# icy-gecko.net
KiCad netlist of a schematic drawn in EAGLE
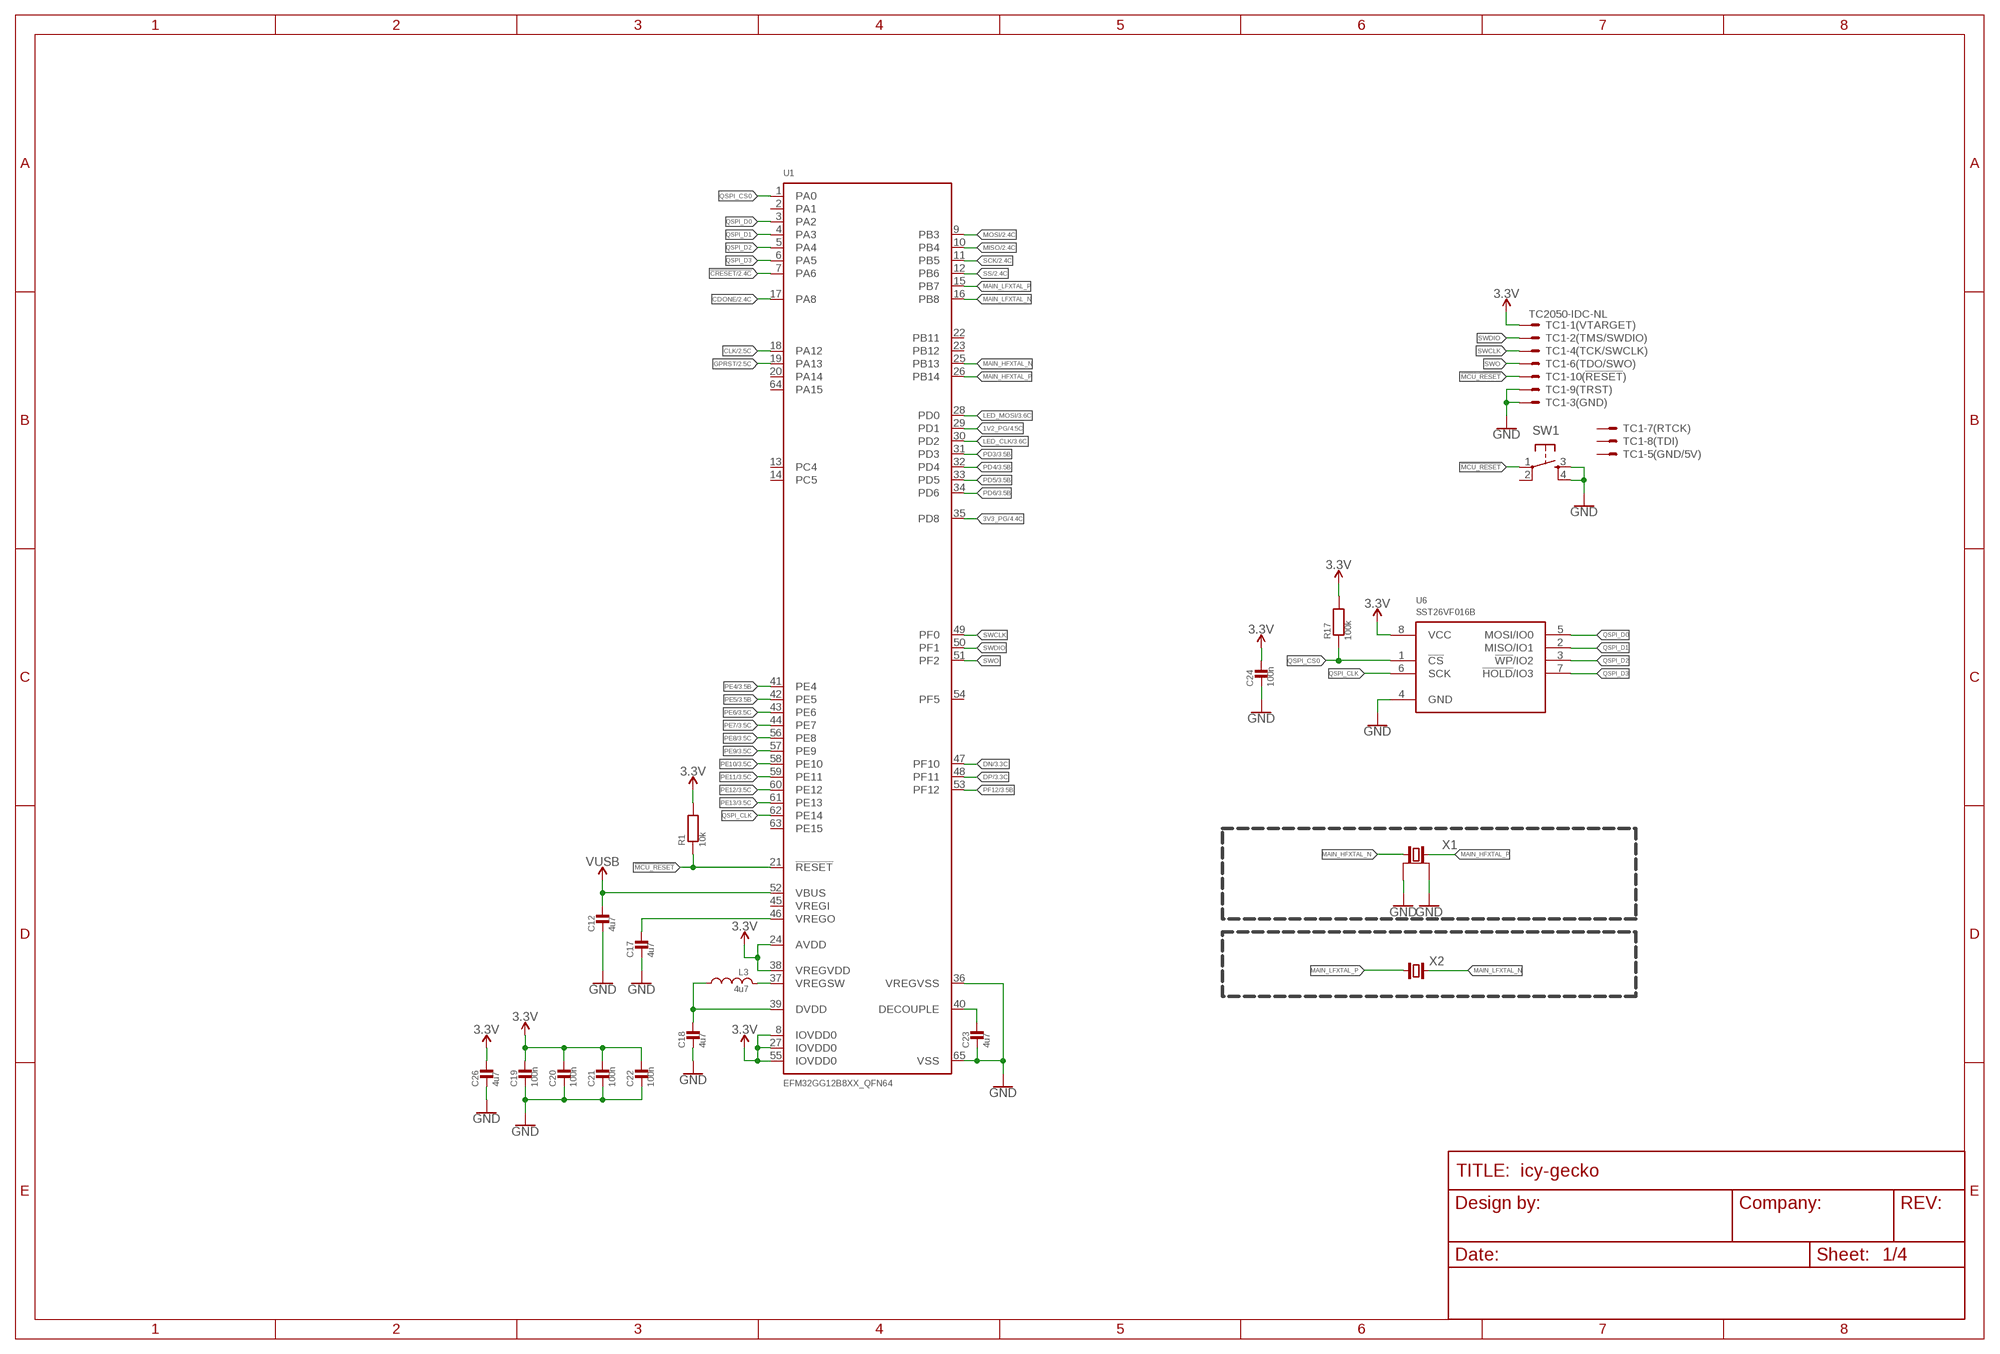
[diagram p0: schematic, sheet 1]
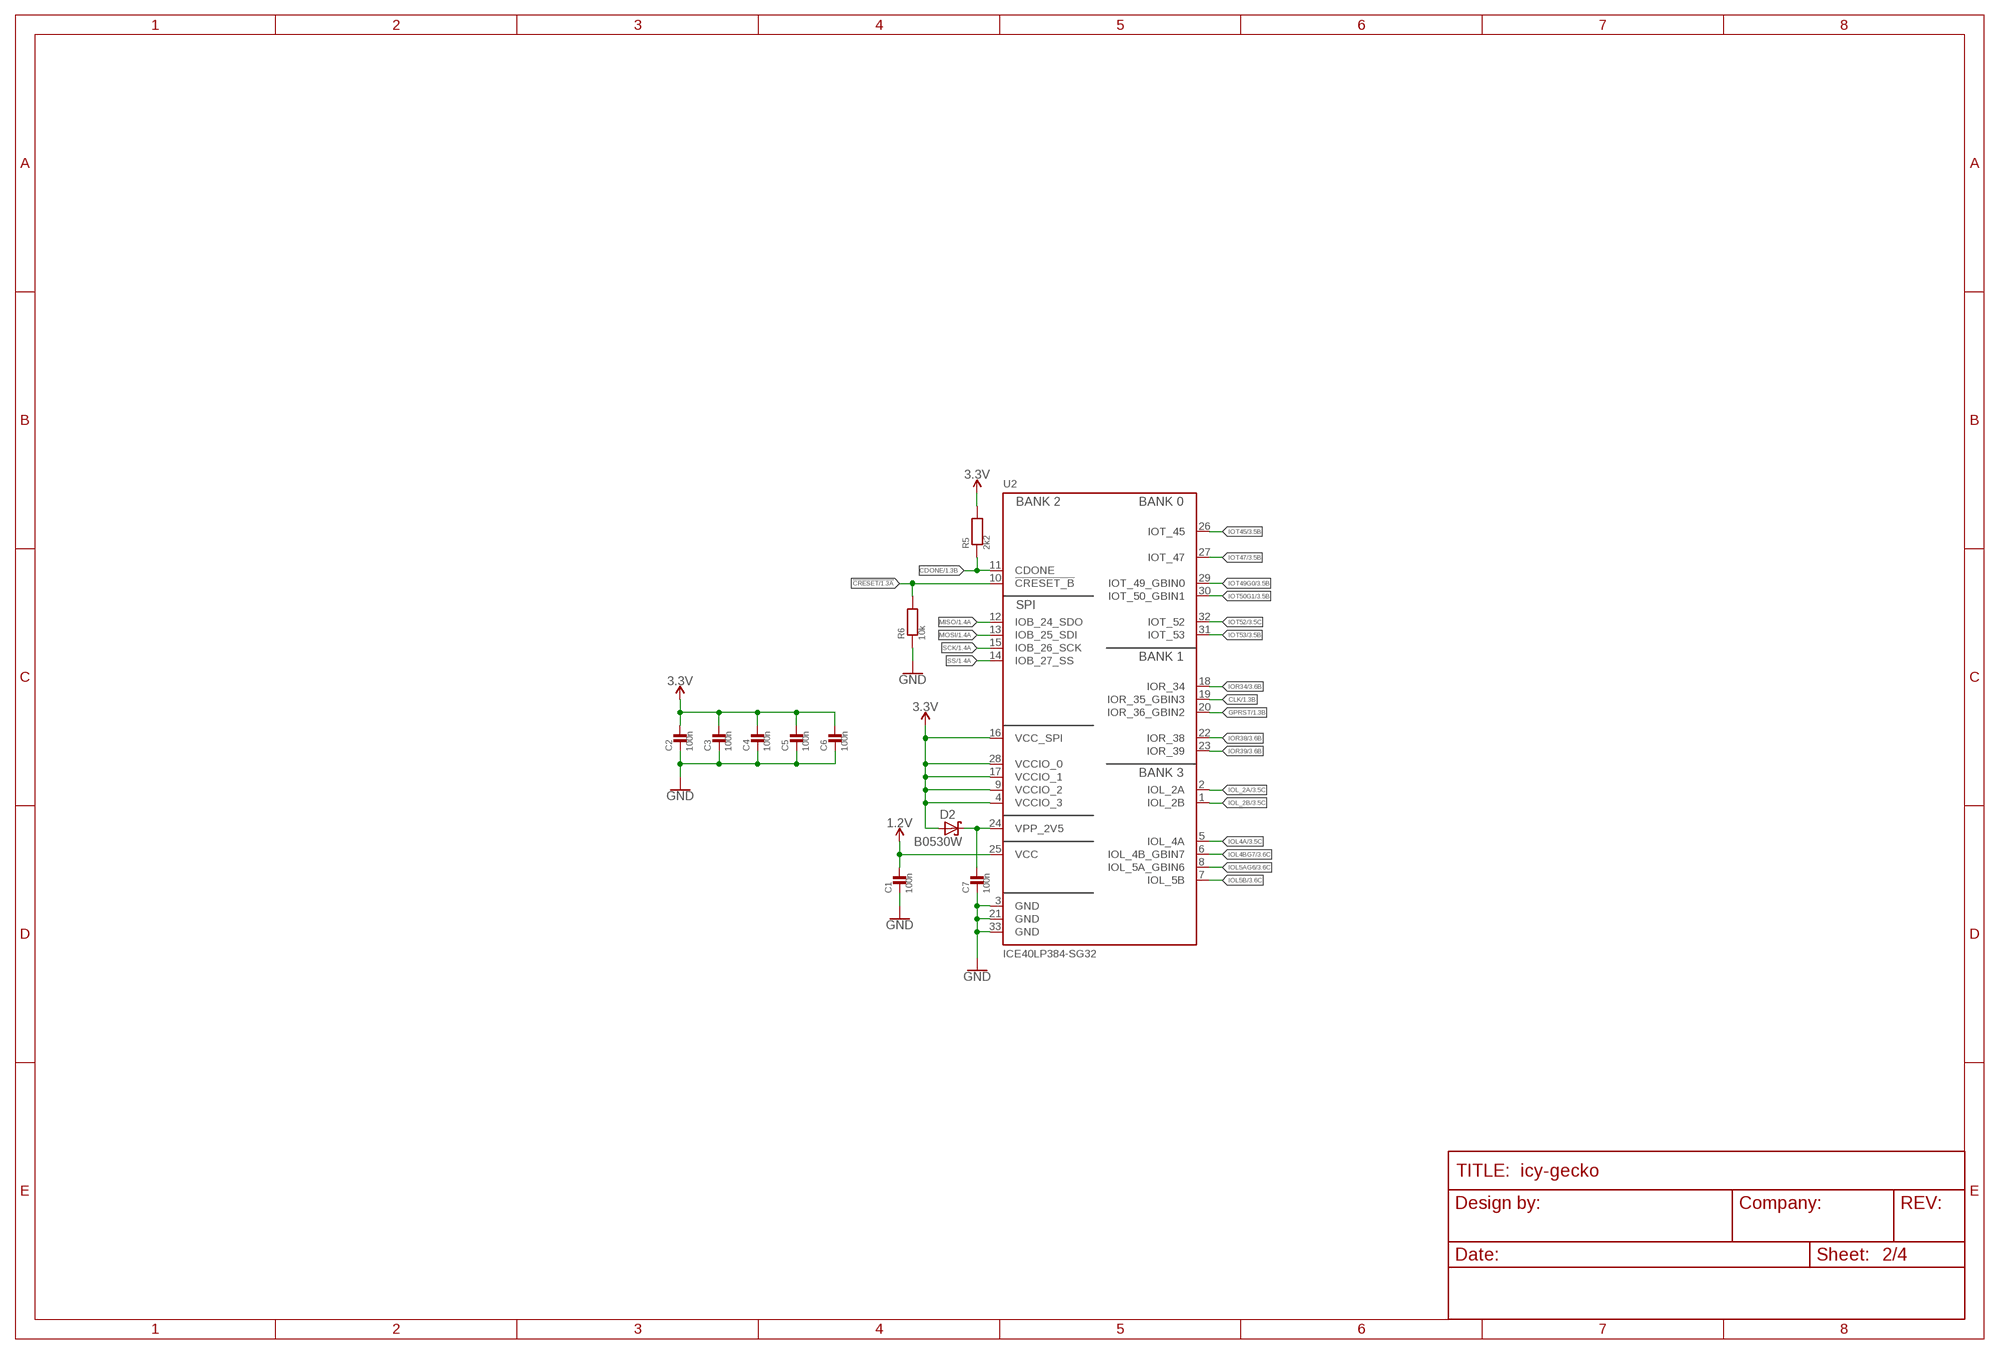
[diagram p1: schematic, sheet 2]
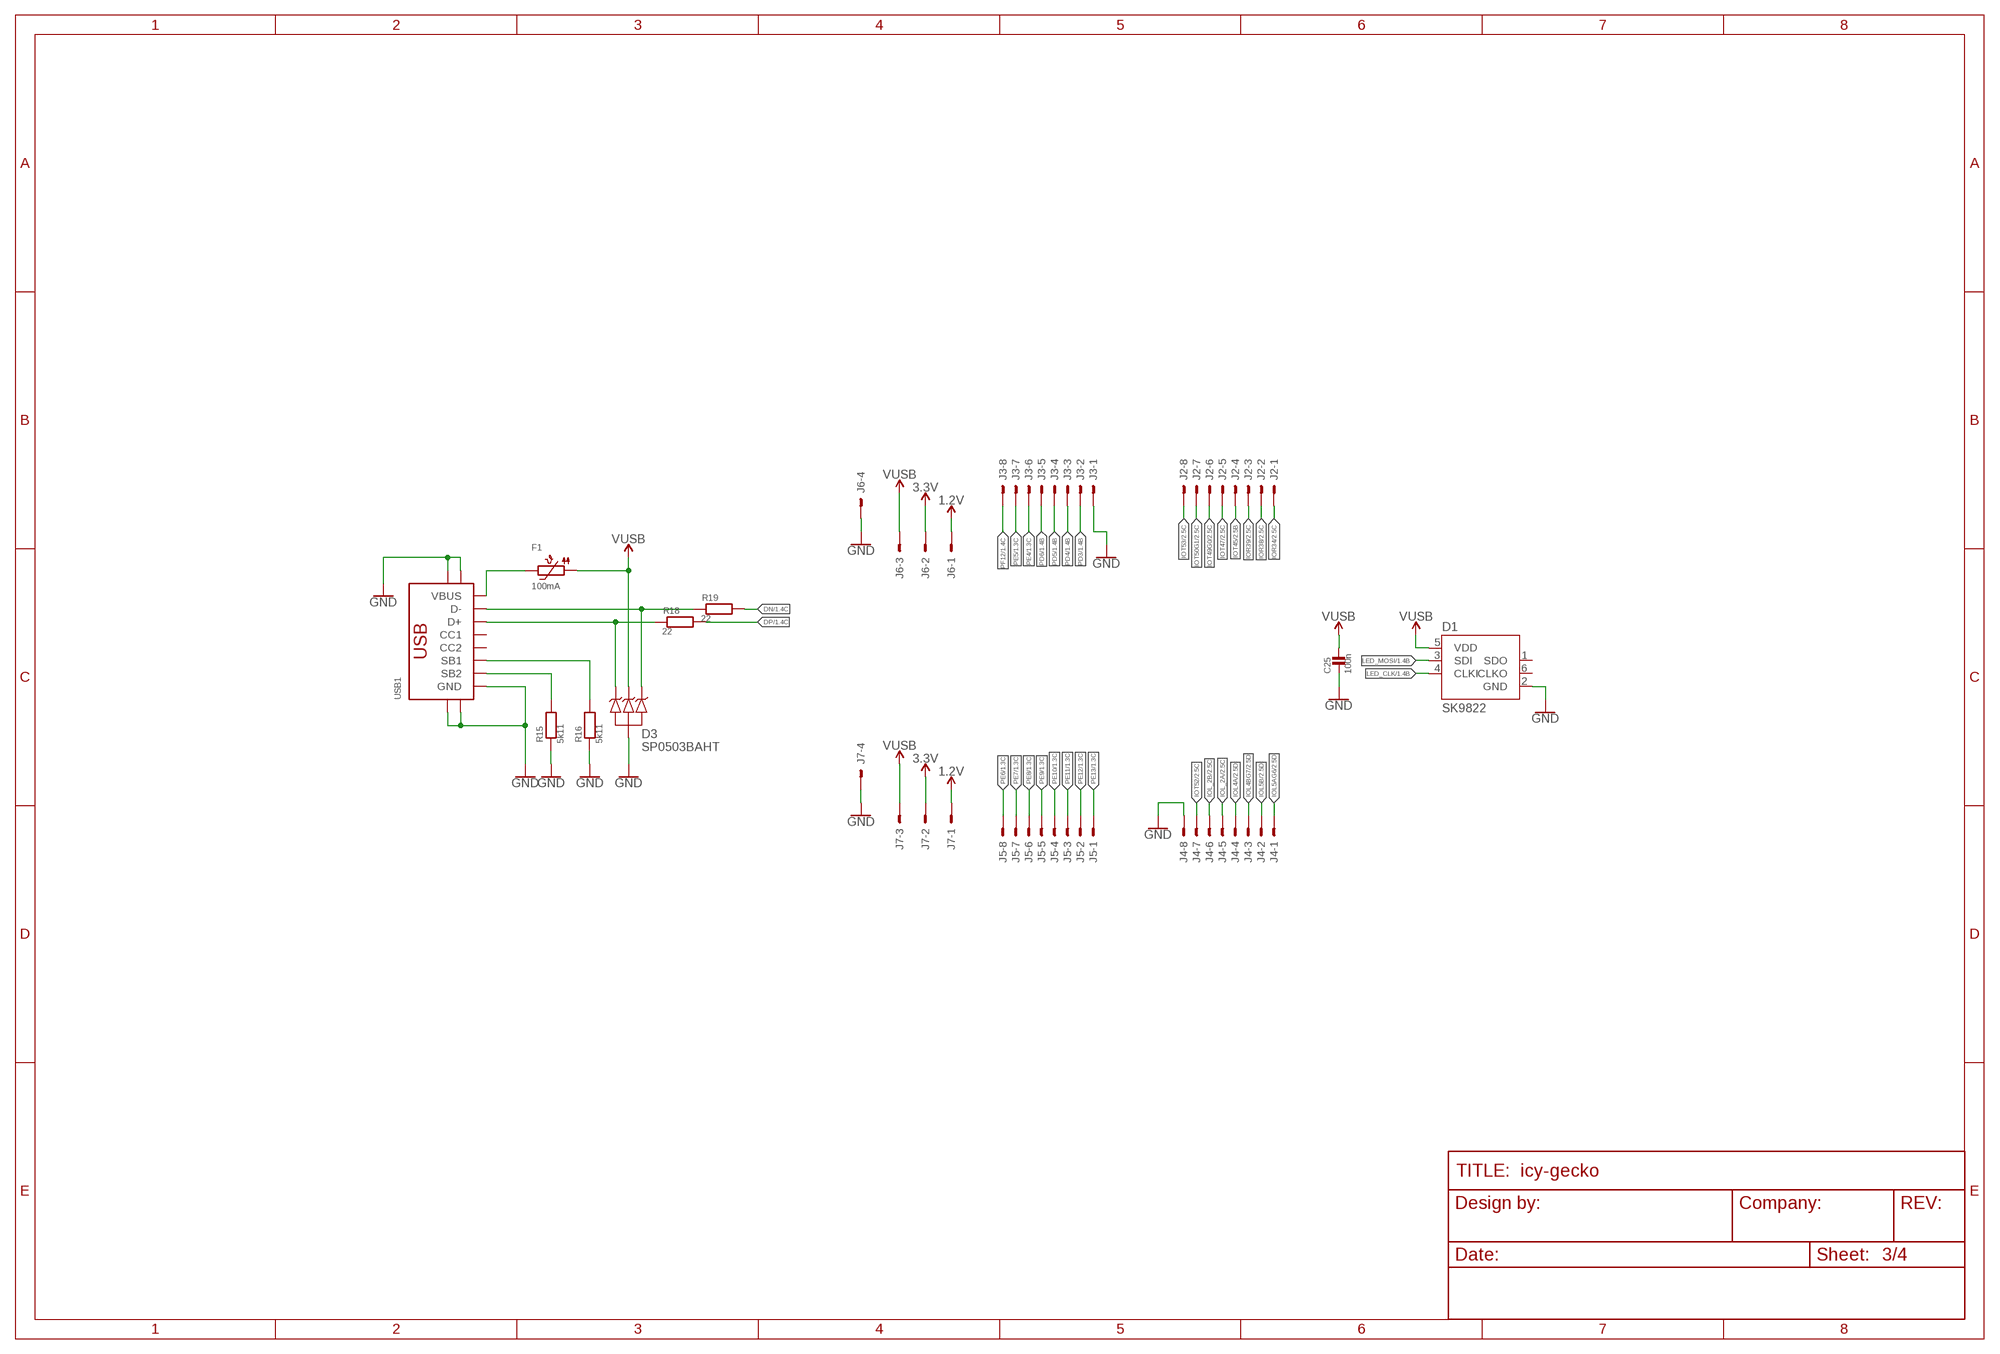
[diagram p2: schematic, sheet 3]
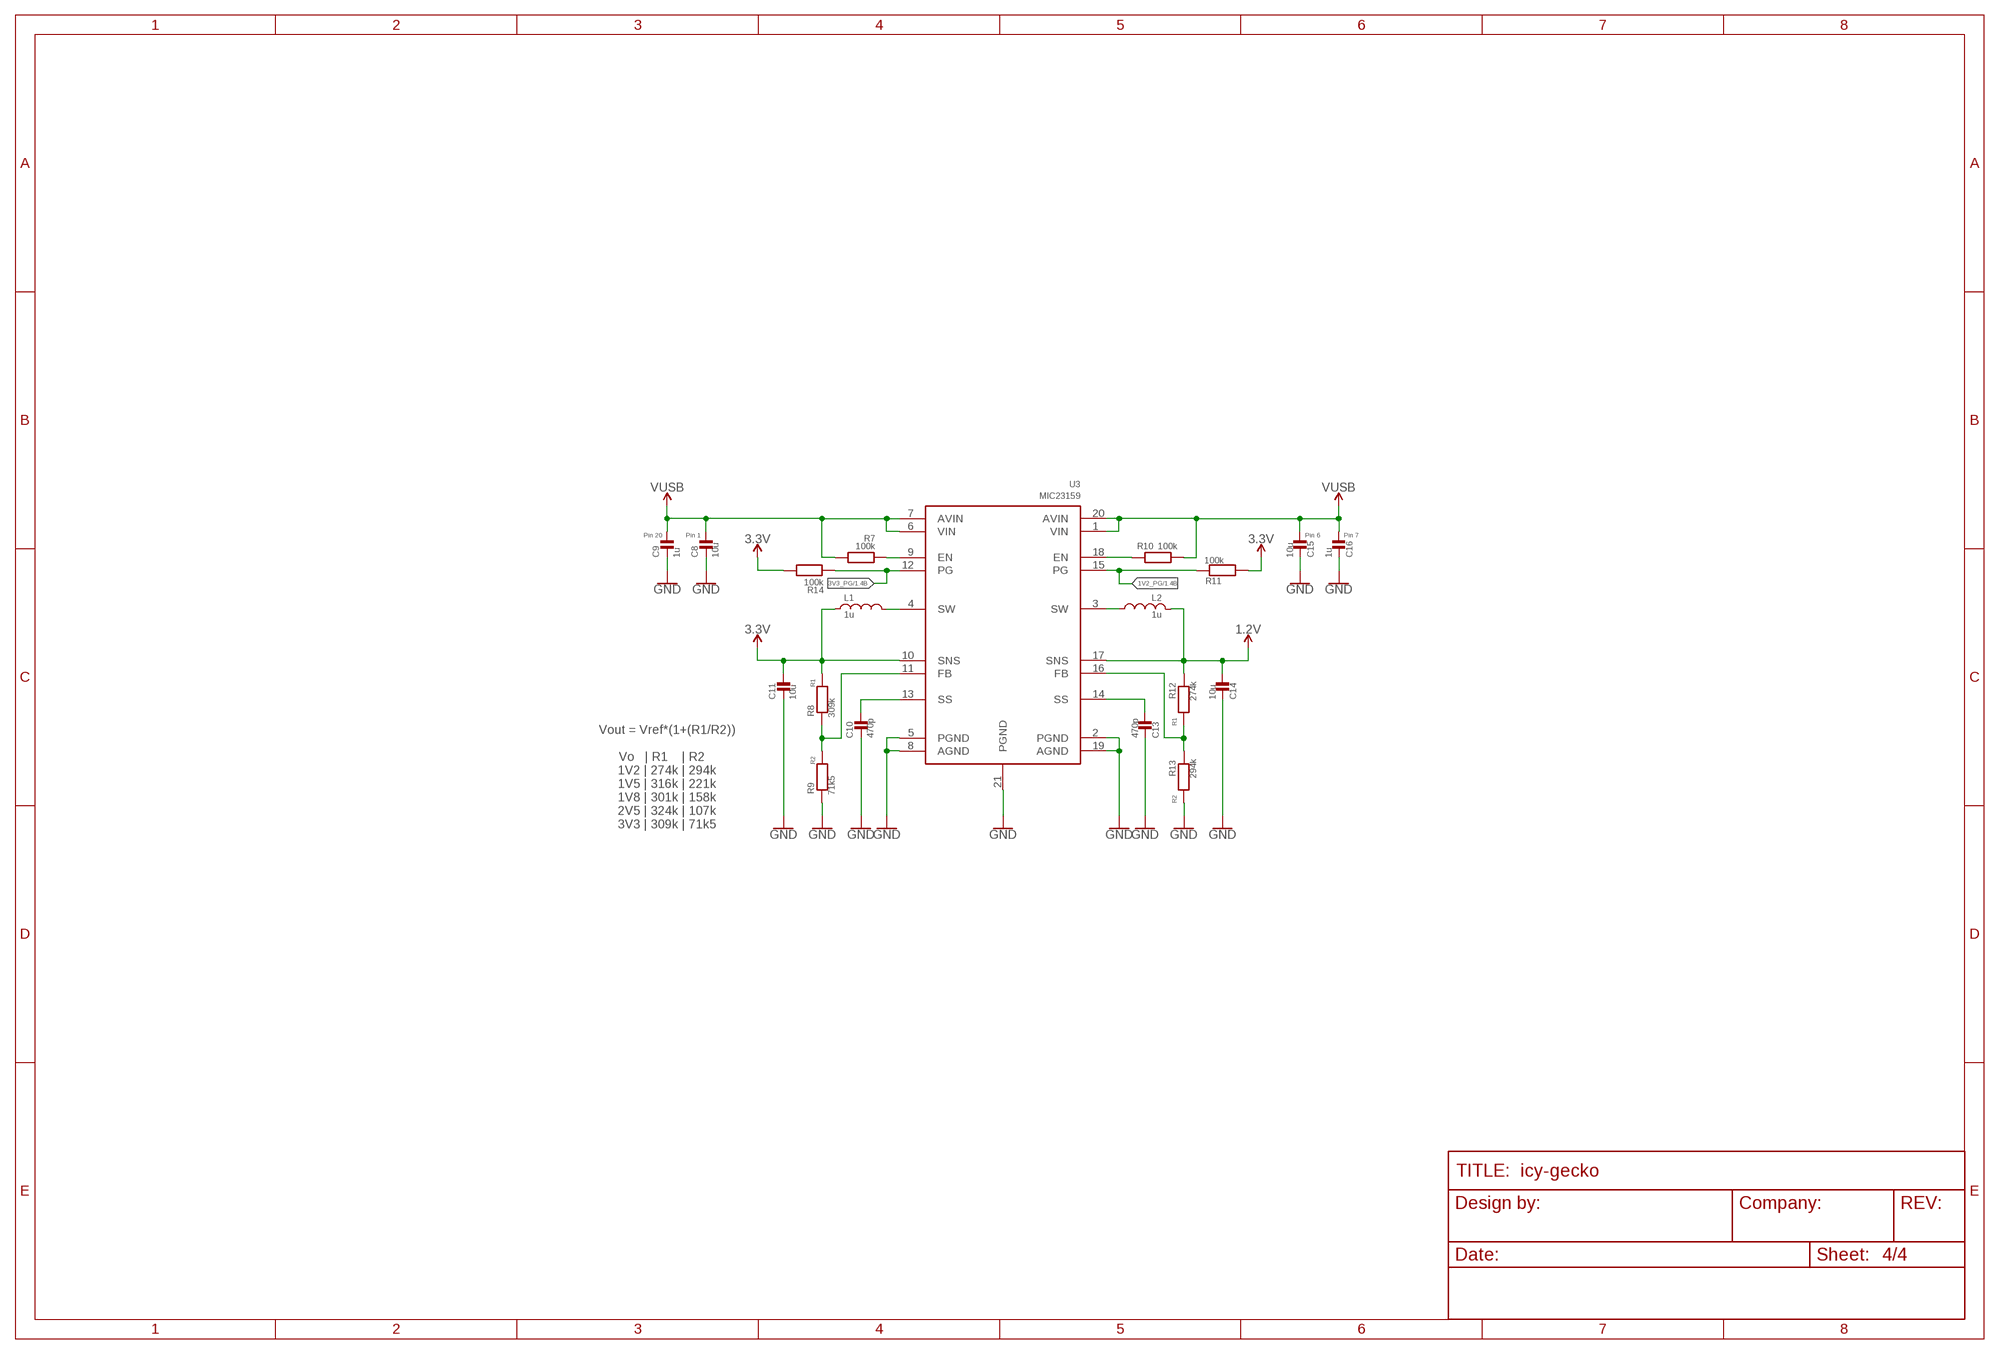
[diagram p3: schematic, sheet 4]

(export (version "E")
  (design (tool "Eeschema 10.0.6"))
  (components
    (comp (ref "C25")
      (value "100n")
      (footprint "eagle-import:0603_WAVE")
      (libsource (lib "eagle-import") (part "MLCC0603"))
    )
    (comp (ref "D1")
      (value "SK9822")
      (footprint "eagle-import:2020")
      (libsource (lib "eagle-import") (part "SK9822"))
    )
    (comp (ref "D3")
      (value "SP0503BAHT")
      (footprint "eagle-import:SOT143")
      (libsource (lib "eagle-import") (part "SP0503BAHT"))
    )
    (comp (ref "F1")
      (value "100mA")
      (footprint "eagle-import:0805")
      (libsource (lib "eagle-import") (part "PTC0805"))
    )
    (comp (ref "J2")
      (value "8")
      (footprint "eagle-import:1X8_2.54")
      (libsource (lib "eagle-import") (part "8"))
    )
    (comp (ref "J3")
      (value "8")
      (footprint "eagle-import:1X8_2.54")
      (libsource (lib "eagle-import") (part "8"))
    )
    (comp (ref "J4")
      (value "8")
      (footprint "eagle-import:1X8_2.54")
      (libsource (lib "eagle-import") (part "8"))
    )
    (comp (ref "J5")
      (value "8")
      (footprint "eagle-import:1X8_2.54")
      (libsource (lib "eagle-import") (part "8"))
    )
    (comp (ref "J6")
      (value "4")
      (footprint "eagle-import:1X4_2.54")
      (libsource (lib "eagle-import") (part "4"))
    )
    (comp (ref "J7")
      (value "4")
      (footprint "eagle-import:1X4_2.54")
      (libsource (lib "eagle-import") (part "4"))
    )
    (comp (ref "R15")
      (value "5k11")
      (footprint "eagle-import:0603_WAVE")
      (libsource (lib "eagle-import") (part "RESISTOR0603"))
    )
    (comp (ref "R16")
      (value "5k11")
      (footprint "eagle-import:0603_WAVE")
      (libsource (lib "eagle-import") (part "RESISTOR0603"))
    )
    (comp (ref "R18")
      (value "22")
      (footprint "eagle-import:0603_WAVE")
      (libsource (lib "eagle-import") (part "RESISTOR0603"))
    )
    (comp (ref "R19")
      (value "22")
      (footprint "eagle-import:0603_WAVE")
      (libsource (lib "eagle-import") (part "RESISTOR0603"))
    )
    (comp (ref "USB1")
      (value "USB-C-16P-SMD-FLAT-SIDE-TYPE-2")
      (footprint "eagle-import:USB-C-16P-SMD-FLAT-SIDE-TYPE-2")
      (libsource (lib "eagle-import") (part "USB-C-16P-SMD-FLAT-SIDE-TYPE-2"))
    )
    (comp (ref "C1")
      (value "100n")
      (footprint "eagle-import:0603_WAVE")
      (libsource (lib "eagle-import") (part "MLCC0603"))
    )
    (comp (ref "C2")
      (value "100n")
      (footprint "eagle-import:0603_WAVE")
      (libsource (lib "eagle-import") (part "MLCC0603"))
    )
    (comp (ref "C3")
      (value "100n")
      (footprint "eagle-import:0603_WAVE")
      (libsource (lib "eagle-import") (part "MLCC0603"))
    )
    (comp (ref "C4")
      (value "100n")
      (footprint "eagle-import:0603_WAVE")
      (libsource (lib "eagle-import") (part "MLCC0603"))
    )
    (comp (ref "C5")
      (value "100n")
      (footprint "eagle-import:0603_WAVE")
      (libsource (lib "eagle-import") (part "MLCC0603"))
    )
    (comp (ref "C6")
      (value "100n")
      (footprint "eagle-import:0603_WAVE")
      (libsource (lib "eagle-import") (part "MLCC0603"))
    )
    (comp (ref "C7")
      (value "100n")
      (footprint "eagle-import:0603_WAVE")
      (libsource (lib "eagle-import") (part "MLCC0603"))
    )
    (comp (ref "D2")
      (value "B0530W")
      (footprint "eagle-import:SOD-123")
      (libsource (lib "eagle-import") (part "B0530W"))
    )
    (comp (ref "R5")
      (value "2k2")
      (footprint "eagle-import:0603_WAVE")
      (libsource (lib "eagle-import") (part "RESISTOR0603"))
    )
    (comp (ref "R6")
      (value "10k")
      (footprint "eagle-import:0603_WAVE")
      (libsource (lib "eagle-import") (part "RESISTOR0603"))
    )
    (comp (ref "U2")
      (value "ICE40LP384-SG32")
      (footprint "eagle-import:QFN32")
      (libsource (lib "eagle-import") (part "ICE40LP384-SG32"))
    )
    (comp (ref "C12")
      (value "4u7")
      (footprint "eagle-import:0603_WAVE")
      (libsource (lib "eagle-import") (part "MLCC0603"))
    )
    (comp (ref "C17")
      (value "4u7")
      (footprint "eagle-import:0603_WAVE")
      (libsource (lib "eagle-import") (part "MLCC0603"))
    )
    (comp (ref "C18")
      (value "4u7")
      (footprint "eagle-import:0603_WAVE")
      (libsource (lib "eagle-import") (part "MLCC0603"))
    )
    (comp (ref "C19")
      (value "100n")
      (footprint "eagle-import:0603_WAVE")
      (libsource (lib "eagle-import") (part "MLCC0603"))
    )
    (comp (ref "C20")
      (value "100n")
      (footprint "eagle-import:0603_WAVE")
      (libsource (lib "eagle-import") (part "MLCC0603"))
    )
    (comp (ref "C21")
      (value "100n")
      (footprint "eagle-import:0603_WAVE")
      (libsource (lib "eagle-import") (part "MLCC0603"))
    )
    (comp (ref "C22")
      (value "100n")
      (footprint "eagle-import:0603_WAVE")
      (libsource (lib "eagle-import") (part "MLCC0603"))
    )
    (comp (ref "C23")
      (value "4u7")
      (footprint "eagle-import:0603_WAVE")
      (libsource (lib "eagle-import") (part "MLCC0603"))
    )
    (comp (ref "C24")
      (value "100n")
      (footprint "eagle-import:0603_WAVE")
      (libsource (lib "eagle-import") (part "MLCC0603"))
    )
    (comp (ref "C26")
      (value "4u7")
      (footprint "eagle-import:0603_WAVE")
      (libsource (lib "eagle-import") (part "MLCC0603"))
    )
    (comp (ref "L3")
      (value "4u7")
      (footprint "eagle-import:_0806")
      (libsource (lib "eagle-import") (part "INDUCTOR_NC_0806"))
    )
    (comp (ref "R1")
      (value "10k")
      (footprint "eagle-import:0603_WAVE")
      (libsource (lib "eagle-import") (part "RESISTOR0603"))
    )
    (comp (ref "R17")
      (value "100k")
      (footprint "eagle-import:0603_WAVE")
      (libsource (lib "eagle-import") (part "RESISTOR0603"))
    )
    (comp (ref "SW1")
      (value "PUSH_BUTTON")
      (footprint "eagle-import:PUSH_BUTTON")
      (libsource (lib "eagle-import") (part "PUSH_BUTTON"))
    )
    (comp (ref "TC1")
      (value "TC2050-IDC-NL")
      (footprint "eagle-import:TC2050-IDC-NL")
      (libsource (lib "eagle-import") (part "TC2050-IDC-NL"))
    )
    (comp (ref "U1")
      (value "EFM32GG12B8XX_QFN64")
      (footprint "eagle-import:QFN64")
      (libsource (lib "eagle-import") (part "EFM32GG12B8XX_QFN64"))
    )
    (comp (ref "U6")
      (value "SST26VF016B")
      (footprint "eagle-import:WSOIC8")
      (libsource (lib "eagle-import") (part "SST26VF016B"))
    )
    (comp (ref "X1")
      (value "CRYSTAL_4P")
      (footprint "eagle-import:4-SMD-3225")
      (libsource (lib "eagle-import") (part "CRYSTAL_4P"))
    )
    (comp (ref "X2")
      (value "CRYSTAL2-SMD-3215")
      (footprint "eagle-import:2-SMD-3215")
      (libsource (lib "eagle-import") (part "CRYSTAL2-SMD-3215"))
    )
    (comp (ref "C8")
      (value "10u")
      (footprint "eagle-import:0603_WAVE")
      (libsource (lib "eagle-import") (part "MLCC0603"))
    )
    (comp (ref "C9")
      (value "1u")
      (footprint "eagle-import:0603_WAVE")
      (libsource (lib "eagle-import") (part "MLCC0603"))
    )
    (comp (ref "C10")
      (value "470p")
      (footprint "eagle-import:0603_WAVE")
      (libsource (lib "eagle-import") (part "MLCC0603"))
    )
    (comp (ref "C11")
      (value "10u")
      (footprint "eagle-import:0603_WAVE")
      (libsource (lib "eagle-import") (part "MLCC0603"))
    )
    (comp (ref "C13")
      (value "470p")
      (footprint "eagle-import:0603_WAVE")
      (libsource (lib "eagle-import") (part "MLCC0603"))
    )
    (comp (ref "C14")
      (value "10u")
      (footprint "eagle-import:0603_WAVE")
      (libsource (lib "eagle-import") (part "MLCC0603"))
    )
    (comp (ref "C15")
      (value "10u")
      (footprint "eagle-import:0603_WAVE")
      (libsource (lib "eagle-import") (part "MLCC0603"))
    )
    (comp (ref "C16")
      (value "1u")
      (footprint "eagle-import:0603_WAVE")
      (libsource (lib "eagle-import") (part "MLCC0603"))
    )
    (comp (ref "L1")
      (value "1u")
      (footprint "eagle-import:_0806")
      (libsource (lib "eagle-import") (part "INDUCTOR_NC_0806"))
    )
    (comp (ref "L2")
      (value "1u")
      (footprint "eagle-import:_0806")
      (libsource (lib "eagle-import") (part "INDUCTOR_NC_0806"))
    )
    (comp (ref "R7")
      (value "100k")
      (footprint "eagle-import:0603_WAVE")
      (libsource (lib "eagle-import") (part "RESISTOR0603"))
    )
    (comp (ref "R8")
      (value "309k")
      (footprint "eagle-import:0603_WAVE")
      (libsource (lib "eagle-import") (part "RESISTOR0603"))
    )
    (comp (ref "R9")
      (value "71k5")
      (footprint "eagle-import:0603_WAVE")
      (libsource (lib "eagle-import") (part "RESISTOR0603"))
    )
    (comp (ref "R10")
      (value "100k")
      (footprint "eagle-import:0603_WAVE")
      (libsource (lib "eagle-import") (part "RESISTOR0603"))
    )
    (comp (ref "R11")
      (value "100k")
      (footprint "eagle-import:0603_WAVE")
      (libsource (lib "eagle-import") (part "RESISTOR0603"))
    )
    (comp (ref "R12")
      (value "274k")
      (footprint "eagle-import:0603_WAVE")
      (libsource (lib "eagle-import") (part "RESISTOR0603"))
    )
    (comp (ref "R13")
      (value "294k")
      (footprint "eagle-import:0603_WAVE")
      (libsource (lib "eagle-import") (part "RESISTOR0603"))
    )
    (comp (ref "R14")
      (value "100k")
      (footprint "eagle-import:0603_WAVE")
      (libsource (lib "eagle-import") (part "RESISTOR0603"))
    )
    (comp (ref "U3")
      (value "MIC23159")
      (footprint "eagle-import:VQFN20")
      (libsource (lib "eagle-import") (part "MIC23159"))
    )
  )
  (nets
    (net (code "1") (name "1.2V") (class "Default")
      (node (ref "C1") (pin "P$1") (pinfunction "P$1_P$1") (pintype "bidirectional"))
      (node (ref "C14") (pin "P$1") (pinfunction "P$1_P$1") (pintype "bidirectional"))
      (node (ref "J6") (pin "1") (pinfunction "S_1") (pintype "passive"))
      (node (ref "J7") (pin "1") (pinfunction "S_1") (pintype "passive"))
      (node (ref "L2") (pin "1") (pinfunction "P$1_1") (pintype "bidirectional"))
      (node (ref "R12") (pin "P$1") (pinfunction "P$1_P$1") (pintype "bidirectional"))
      (node (ref "U2") (pin "25") (pinfunction "VCC_25") (pintype "bidirectional"))
      (node (ref "U3") (pin "17") (pinfunction "SNS_17") (pintype "bidirectional"))
    )
    (net (code "2") (name "1V2_PG") (class "Default")
      (node (ref "R11") (pin "P$1") (pinfunction "P$1_P$1") (pintype "bidirectional"))
      (node (ref "U1") (pin "29") (pinfunction "PD1_29") (pintype "bidirectional"))
      (node (ref "U3") (pin "15") (pinfunction "PG_15") (pintype "bidirectional"))
    )
    (net (code "3") (name "3.3V") (class "Default")
      (node (ref "C11") (pin "P$1") (pinfunction "P$1_P$1") (pintype "bidirectional"))
      (node (ref "C19") (pin "P$1") (pinfunction "P$1_P$1") (pintype "bidirectional"))
      (node (ref "C2") (pin "P$1") (pinfunction "P$1_P$1") (pintype "bidirectional"))
      (node (ref "C20") (pin "P$1") (pinfunction "P$1_P$1") (pintype "bidirectional"))
      (node (ref "C21") (pin "P$1") (pinfunction "P$1_P$1") (pintype "bidirectional"))
      (node (ref "C22") (pin "P$1") (pinfunction "P$1_P$1") (pintype "bidirectional"))
      (node (ref "C24") (pin "P$1") (pinfunction "P$1_P$1") (pintype "bidirectional"))
      (node (ref "C26") (pin "P$1") (pinfunction "P$1_P$1") (pintype "bidirectional"))
      (node (ref "C3") (pin "P$1") (pinfunction "P$1_P$1") (pintype "bidirectional"))
      (node (ref "C4") (pin "P$1") (pinfunction "P$1_P$1") (pintype "bidirectional"))
      (node (ref "C5") (pin "P$1") (pinfunction "P$1_P$1") (pintype "bidirectional"))
      (node (ref "C6") (pin "P$1") (pinfunction "P$1_P$1") (pintype "bidirectional"))
      (node (ref "D2") (pin "A") (pinfunction "A_A") (pintype "passive"))
      (node (ref "J6") (pin "2") (pinfunction "S_2") (pintype "passive"))
      (node (ref "J7") (pin "2") (pinfunction "S_2") (pintype "passive"))
      (node (ref "L1") (pin "1") (pinfunction "P$1_1") (pintype "bidirectional"))
      (node (ref "R1") (pin "P$2") (pinfunction "P$2_P$2") (pintype "bidirectional"))
      (node (ref "R11") (pin "P$2") (pinfunction "P$2_P$2") (pintype "bidirectional"))
      (node (ref "R14") (pin "P$2") (pinfunction "P$2_P$2") (pintype "bidirectional"))
      (node (ref "R17") (pin "P$2") (pinfunction "P$2_P$2") (pintype "bidirectional"))
      (node (ref "R5") (pin "P$2") (pinfunction "P$2_P$2") (pintype "bidirectional"))
      (node (ref "R8") (pin "P$2") (pinfunction "P$2_P$2") (pintype "bidirectional"))
      (node (ref "TC1") (pin "1") (pinfunction "S_1") (pintype "passive"))
      (node (ref "U1") (pin "24") (pinfunction "AVDD_24") (pintype "bidirectional"))
      (node (ref "U1") (pin "27") (pinfunction "IOVDD0_27") (pintype "bidirectional"))
      (node (ref "U1") (pin "38") (pinfunction "VREGVDD_38") (pintype "bidirectional"))
      (node (ref "U1") (pin "55") (pinfunction "IOVDD0_55") (pintype "bidirectional"))
      (node (ref "U1") (pin "8") (pinfunction "IOVDD0_8") (pintype "bidirectional"))
      (node (ref "U2") (pin "16") (pinfunction "VCC_SPI_16") (pintype "bidirectional"))
      (node (ref "U2") (pin "17") (pinfunction "VCCIO_1_17") (pintype "bidirectional"))
      (node (ref "U2") (pin "28") (pinfunction "VCCIO_0_28") (pintype "bidirectional"))
      (node (ref "U2") (pin "4") (pinfunction "VCCIO_3_4") (pintype "bidirectional"))
      (node (ref "U2") (pin "9") (pinfunction "VCCIO_2_9") (pintype "bidirectional"))
      (node (ref "U3") (pin "10") (pinfunction "SNS_10") (pintype "bidirectional"))
      (node (ref "U6") (pin "8") (pinfunction "VCC_8") (pintype "power_in"))
    )
    (net (code "4") (name "3V3_PG") (class "Default")
      (node (ref "R14") (pin "P$1") (pinfunction "P$1_P$1") (pintype "bidirectional"))
      (node (ref "U1") (pin "35") (pinfunction "PD8_35") (pintype "bidirectional"))
      (node (ref "U3") (pin "12") (pinfunction "PG_12") (pintype "bidirectional"))
    )
    (net (code "5") (name "CDONE") (class "Default")
      (node (ref "R5") (pin "P$1") (pinfunction "P$1_P$1") (pintype "bidirectional"))
      (node (ref "U1") (pin "17") (pinfunction "PA8_17") (pintype "bidirectional"))
      (node (ref "U2") (pin "11") (pinfunction "CDONE_11") (pintype "bidirectional"))
    )
    (net (code "6") (name "CLK") (class "Default")
      (node (ref "U1") (pin "18") (pinfunction "PA12_18") (pintype "bidirectional"))
      (node (ref "U2") (pin "19") (pinfunction "IOR_35_GBIN3_19") (pintype "bidirectional"))
    )
    (net (code "7") (name "DN") (class "Default")
      (node (ref "R19") (pin "P$2") (pinfunction "P$2_P$2") (pintype "bidirectional"))
      (node (ref "U1") (pin "47") (pinfunction "PF10_47") (pintype "bidirectional"))
    )
    (net (code "8") (name "DP") (class "Default")
      (node (ref "R18") (pin "P$2") (pinfunction "P$2_P$2") (pintype "bidirectional"))
      (node (ref "U1") (pin "48") (pinfunction "PF11_48") (pintype "bidirectional"))
    )
    (net (code "9") (name "GND") (class "Default")
      (node (ref "C1") (pin "P$2") (pinfunction "P$2_P$2") (pintype "bidirectional"))
      (node (ref "C10") (pin "P$2") (pinfunction "P$2_P$2") (pintype "bidirectional"))
      (node (ref "C11") (pin "P$2") (pinfunction "P$2_P$2") (pintype "bidirectional"))
      (node (ref "C12") (pin "P$2") (pinfunction "P$2_P$2") (pintype "bidirectional"))
      (node (ref "C13") (pin "P$2") (pinfunction "P$2_P$2") (pintype "bidirectional"))
      (node (ref "C14") (pin "P$2") (pinfunction "P$2_P$2") (pintype "bidirectional"))
      (node (ref "C15") (pin "P$2") (pinfunction "P$2_P$2") (pintype "bidirectional"))
      (node (ref "C16") (pin "P$2") (pinfunction "P$2_P$2") (pintype "bidirectional"))
      (node (ref "C17") (pin "P$2") (pinfunction "P$2_P$2") (pintype "bidirectional"))
      (node (ref "C18") (pin "P$2") (pinfunction "P$2_P$2") (pintype "bidirectional"))
      (node (ref "C19") (pin "P$2") (pinfunction "P$2_P$2") (pintype "bidirectional"))
      (node (ref "C2") (pin "P$2") (pinfunction "P$2_P$2") (pintype "bidirectional"))
      (node (ref "C20") (pin "P$2") (pinfunction "P$2_P$2") (pintype "bidirectional"))
      (node (ref "C21") (pin "P$2") (pinfunction "P$2_P$2") (pintype "bidirectional"))
      (node (ref "C22") (pin "P$2") (pinfunction "P$2_P$2") (pintype "bidirectional"))
      (node (ref "C23") (pin "P$2") (pinfunction "P$2_P$2") (pintype "bidirectional"))
      (node (ref "C24") (pin "P$2") (pinfunction "P$2_P$2") (pintype "bidirectional"))
      (node (ref "C25") (pin "P$2") (pinfunction "P$2_P$2") (pintype "bidirectional"))
      (node (ref "C26") (pin "P$2") (pinfunction "P$2_P$2") (pintype "bidirectional"))
      (node (ref "C3") (pin "P$2") (pinfunction "P$2_P$2") (pintype "bidirectional"))
      (node (ref "C4") (pin "P$2") (pinfunction "P$2_P$2") (pintype "bidirectional"))
      (node (ref "C5") (pin "P$2") (pinfunction "P$2_P$2") (pintype "bidirectional"))
      (node (ref "C6") (pin "P$2") (pinfunction "P$2_P$2") (pintype "bidirectional"))
      (node (ref "C7") (pin "P$2") (pinfunction "P$2_P$2") (pintype "bidirectional"))
      (node (ref "C8") (pin "P$2") (pinfunction "P$2_P$2") (pintype "bidirectional"))
      (node (ref "C9") (pin "P$2") (pinfunction "P$2_P$2") (pintype "bidirectional"))
      (node (ref "D1") (pin "2") (pinfunction "GND_2") (pintype "bidirectional"))
      (node (ref "D3") (pin "1") (pinfunction "1_1") (pintype "bidirectional"))
      (node (ref "J3") (pin "1") (pinfunction "S_1") (pintype "passive"))
      (node (ref "J4") (pin "8") (pinfunction "S_8") (pintype "passive"))
      (node (ref "J6") (pin "4") (pinfunction "S_4") (pintype "passive"))
      (node (ref "J7") (pin "4") (pinfunction "S_4") (pintype "passive"))
      (node (ref "R13") (pin "P$2") (pinfunction "P$2_P$2") (pintype "bidirectional"))
      (node (ref "R15") (pin "P$1") (pinfunction "P$1_P$1") (pintype "bidirectional"))
      (node (ref "R16") (pin "P$1") (pinfunction "P$1_P$1") (pintype "bidirectional"))
      (node (ref "R6") (pin "P$1") (pinfunction "P$1_P$1") (pintype "bidirectional"))
      (node (ref "R9") (pin "P$1") (pinfunction "P$1_P$1") (pintype "bidirectional"))
      (node (ref "SW1") (pin "3") (pinfunction "3_3") (pintype "passive"))
      (node (ref "SW1") (pin "4") (pinfunction "4_4") (pintype "passive"))
      (node (ref "TC1") (pin "3") (pinfunction "S_3") (pintype "passive"))
      (node (ref "TC1") (pin "9") (pinfunction "S_9") (pintype "passive"))
      (node (ref "U1") (pin "36") (pinfunction "VREGVSS_36") (pintype "bidirectional"))
      (node (ref "U1") (pin "65") (pinfunction "VSS_65") (pintype "bidirectional"))
      (node (ref "U2") (pin "21") (pinfunction "GND_21") (pintype "bidirectional"))
      (node (ref "U2") (pin "3") (pinfunction "GND_3") (pintype "bidirectional"))
      (node (ref "U2") (pin "33") (pinfunction "GND_33") (pintype "bidirectional"))
      (node (ref "U3") (pin "19") (pinfunction "AGND_19") (pintype "bidirectional"))
      (node (ref "U3") (pin "2") (pinfunction "PGND_2") (pintype "bidirectional"))
      (node (ref "U3") (pin "21") (pinfunction "PGND_21") (pintype "bidirectional"))
      (node (ref "U3") (pin "5") (pinfunction "PGND_5") (pintype "bidirectional"))
      (node (ref "U3") (pin "8") (pinfunction "AGND_8") (pintype "bidirectional"))
      (node (ref "U6") (pin "4") (pinfunction "GND_4") (pintype "power_in"))
      (node (ref "USB1") (pin "A1/B12") (pinfunction "GND_A1/B12") (pintype "bidirectional"))
      (node (ref "USB1") (pin "B1/A12") (pinfunction "GND_B1/A12") (pintype "bidirectional"))
      (node (ref "USB1") (pin "SHIELD@0") (pinfunction "SHIELD_SHIELD@0") (pintype "bidirectional"))
      (node (ref "USB1") (pin "SHIELD@1") (pinfunction "SHIELD_SHIELD@1") (pintype "bidirectional"))
      (node (ref "USB1") (pin "SHIELD@2") (pinfunction "SHIELD_SHIELD@2") (pintype "bidirectional"))
      (node (ref "USB1") (pin "SHIELD@3") (pinfunction "SHIELD_SHIELD@3") (pintype "bidirectional"))
      (node (ref "X1") (pin "2") (pinfunction "GND_2") (pintype "passive"))
      (node (ref "X1") (pin "4") (pinfunction "GND_4") (pintype "passive"))
    )
    (net (code "10") (name "GPRST") (class "Default")
      (node (ref "U1") (pin "19") (pinfunction "PA13_19") (pintype "bidirectional"))
      (node (ref "U2") (pin "20") (pinfunction "IOR_36_GBIN2_20") (pintype "bidirectional"))
    )
    (net (code "11") (name "IOL4A") (class "Default")
      (node (ref "J4") (pin "4") (pinfunction "S_4") (pintype "passive"))
      (node (ref "U2") (pin "5") (pinfunction "IOL_4A_5") (pintype "bidirectional"))
    )
    (net (code "12") (name "IOL4BG7") (class "Default")
      (node (ref "J4") (pin "3") (pinfunction "S_3") (pintype "passive"))
      (node (ref "U2") (pin "6") (pinfunction "IOL_4B_GBIN7_6") (pintype "bidirectional"))
    )
    (net (code "13") (name "IOL5AG6") (class "Default")
      (node (ref "J4") (pin "1") (pinfunction "S_1") (pintype "passive"))
      (node (ref "U2") (pin "8") (pinfunction "IOL_5A_GBIN6_8") (pintype "bidirectional"))
    )
    (net (code "14") (name "IOL5B") (class "Default")
      (node (ref "J4") (pin "2") (pinfunction "S_2") (pintype "passive"))
      (node (ref "U2") (pin "7") (pinfunction "IOL_5B_7") (pintype "bidirectional"))
    )
    (net (code "15") (name "IOL_2A") (class "Default")
      (node (ref "J4") (pin "5") (pinfunction "S_5") (pintype "passive"))
      (node (ref "U2") (pin "2") (pinfunction "IOL_2A_2") (pintype "bidirectional"))
    )
    (net (code "16") (name "IOL_2B") (class "Default")
      (node (ref "J4") (pin "6") (pinfunction "S_6") (pintype "passive"))
      (node (ref "U2") (pin "1") (pinfunction "IOL_2B_1") (pintype "bidirectional"))
    )
    (net (code "17") (name "IOR34") (class "Default")
      (node (ref "J2") (pin "1") (pinfunction "S_1") (pintype "passive"))
      (node (ref "U2") (pin "18") (pinfunction "IOR_34_18") (pintype "bidirectional"))
    )
    (net (code "18") (name "IOR38") (class "Default")
      (node (ref "J2") (pin "2") (pinfunction "S_2") (pintype "passive"))
      (node (ref "U2") (pin "22") (pinfunction "IOR_38_22") (pintype "bidirectional"))
    )
    (net (code "19") (name "IOR39") (class "Default")
      (node (ref "J2") (pin "3") (pinfunction "S_3") (pintype "passive"))
      (node (ref "U2") (pin "23") (pinfunction "IOR_39_23") (pintype "bidirectional"))
    )
    (net (code "20") (name "IOT45") (class "Default")
      (node (ref "J2") (pin "4") (pinfunction "S_4") (pintype "passive"))
      (node (ref "U2") (pin "26") (pinfunction "IOT_45_26") (pintype "bidirectional"))
    )
    (net (code "21") (name "IOT47") (class "Default")
      (node (ref "J2") (pin "5") (pinfunction "S_5") (pintype "passive"))
      (node (ref "U2") (pin "27") (pinfunction "IOT_47_27") (pintype "bidirectional"))
    )
    (net (code "22") (name "IOT49G0") (class "Default")
      (node (ref "J2") (pin "6") (pinfunction "S_6") (pintype "passive"))
      (node (ref "U2") (pin "29") (pinfunction "IOT_49_GBIN0_29") (pintype "bidirectional"))
    )
    (net (code "23") (name "IOT50G1") (class "Default")
      (node (ref "J2") (pin "7") (pinfunction "S_7") (pintype "passive"))
      (node (ref "U2") (pin "30") (pinfunction "IOT_50_GBIN1_30") (pintype "bidirectional"))
    )
    (net (code "24") (name "IOT52") (class "Default")
      (node (ref "J4") (pin "7") (pinfunction "S_7") (pintype "passive"))
      (node (ref "U2") (pin "32") (pinfunction "IOT_52_32") (pintype "bidirectional"))
    )
    (net (code "25") (name "IOT53") (class "Default")
      (node (ref "J2") (pin "8") (pinfunction "S_8") (pintype "passive"))
      (node (ref "U2") (pin "31") (pinfunction "IOT_53_31") (pintype "bidirectional"))
    )
    (net (code "26") (name "LED_CLK") (class "Default")
      (node (ref "D1") (pin "4") (pinfunction "CLKI_4") (pintype "bidirectional"))
      (node (ref "U1") (pin "30") (pinfunction "PD2_30") (pintype "bidirectional"))
    )
    (net (code "27") (name "LED_MOSI") (class "Default")
      (node (ref "D1") (pin "3") (pinfunction "SDI_3") (pintype "bidirectional"))
      (node (ref "U1") (pin "28") (pinfunction "PD0_28") (pintype "bidirectional"))
    )
    (net (code "28") (name "MAIN_HFXTAL_N") (class "Default")
      (node (ref "U1") (pin "25") (pinfunction "PB13_25") (pintype "bidirectional"))
      (node (ref "X1") (pin "1") (pinfunction "1_1") (pintype "passive"))
    )
    (net (code "29") (name "MAIN_HFXTAL_P") (class "Default")
      (node (ref "U1") (pin "26") (pinfunction "PB14_26") (pintype "bidirectional"))
      (node (ref "X1") (pin "3") (pinfunction "2_3") (pintype "passive"))
    )
    (net (code "30") (name "MAIN_LFXTAL_N") (class "Default")
      (node (ref "U1") (pin "16") (pinfunction "PB8_16") (pintype "bidirectional"))
      (node (ref "X2") (pin "2") (pinfunction "2_2") (pintype "passive"))
    )
    (net (code "31") (name "MAIN_LFXTAL_P") (class "Default")
      (node (ref "U1") (pin "15") (pinfunction "PB7_15") (pintype "bidirectional"))
      (node (ref "X2") (pin "1") (pinfunction "1_1") (pintype "passive"))
    )
    (net (code "32") (name "MISO") (class "Default")
      (node (ref "U1") (pin "10") (pinfunction "PB4_10") (pintype "bidirectional"))
      (node (ref "U2") (pin "12") (pinfunction "IOB_24_SDO_12") (pintype "bidirectional"))
    )
    (net (code "33") (name "MOSI") (class "Default")
      (node (ref "U1") (pin "9") (pinfunction "PB3_9") (pintype "bidirectional"))
      (node (ref "U2") (pin "13") (pinfunction "IOB_25_SDI_13") (pintype "bidirectional"))
    )
    (net (code "34") (name "Net-(C10-PadP$1)") (class "Default")
      (node (ref "C10") (pin "P$1") (pinfunction "P$1_P$1") (pintype "bidirectional"))
      (node (ref "U3") (pin "13") (pinfunction "SS_13") (pintype "bidirectional"))
    )
    (net (code "35") (name "Net-(C13-PadP$1)") (class "Default")
      (node (ref "C13") (pin "P$1") (pinfunction "P$1_P$1") (pintype "bidirectional"))
      (node (ref "U3") (pin "14") (pinfunction "SS_14") (pintype "bidirectional"))
    )
    (net (code "36") (name "Net-(D3-Pad2)") (class "Default")
      (node (ref "D3") (pin "2") (pinfunction "2_2") (pintype "bidirectional"))
      (node (ref "R18") (pin "P$1") (pinfunction "P$1_P$1") (pintype "bidirectional"))
      (node (ref "USB1") (pin "A6") (pinfunction "D+_A6") (pintype "bidirectional"))
      (node (ref "USB1") (pin "B6") (pinfunction "D+_B6") (pintype "bidirectional"))
    )
    (net (code "37") (name "Net-(D3-Pad4)") (class "Default")
      (node (ref "D3") (pin "4") (pinfunction "4_4") (pintype "bidirectional"))
      (node (ref "R19") (pin "P$1") (pinfunction "P$1_P$1") (pintype "bidirectional"))
      (node (ref "USB1") (pin "A7") (pinfunction "D-_A7") (pintype "bidirectional"))
      (node (ref "USB1") (pin "B7") (pinfunction "D-_B7") (pintype "bidirectional"))
    )
    (net (code "38") (name "Net-(F1-Pad2)") (class "Default")
      (node (ref "F1") (pin "2") (pinfunction "2_2") (pintype "passive"))
      (node (ref "USB1") (pin "A4/B9") (pinfunction "VBUS_A4/B9") (pintype "bidirectional"))
      (node (ref "USB1") (pin "B4/A9") (pinfunction "VBUS_B4/A9") (pintype "bidirectional"))
    )
    (net (code "39") (name "Net-(L1-P$2)") (class "Default")
      (node (ref "L1") (pin "2") (pinfunction "P$2_2") (pintype "bidirectional"))
      (node (ref "U3") (pin "4") (pinfunction "SW_4") (pintype "bidirectional"))
    )
    (net (code "40") (name "Net-(L2-P$2)") (class "Default")
      (node (ref "L2") (pin "2") (pinfunction "P$2_2") (pintype "bidirectional"))
      (node (ref "U3") (pin "3") (pinfunction "SW_3") (pintype "bidirectional"))
    )
    (net (code "41") (name "Net-(L3-P$1)") (class "Default")
      (node (ref "L3") (pin "1") (pinfunction "P$1_1") (pintype "bidirectional"))
      (node (ref "U1") (pin "37") (pinfunction "VREGSW_37") (pintype "bidirectional"))
    )
    (net (code "42") (name "Net-(L3-P$2)") (class "Default")
      (node (ref "C18") (pin "P$1") (pinfunction "P$1_P$1") (pintype "bidirectional"))
      (node (ref "L3") (pin "2") (pinfunction "P$2_2") (pintype "bidirectional"))
      (node (ref "U1") (pin "39") (pinfunction "DVDD_39") (pintype "bidirectional"))
    )
    (net (code "43") (name "Net-(R7-PadP$1)") (class "Default")
      (node (ref "R7") (pin "P$1") (pinfunction "P$1_P$1") (pintype "bidirectional"))
      (node (ref "U3") (pin "9") (pinfunction "EN_9") (pintype "bidirectional"))
    )
    (net (code "44") (name "Net-(R8-PadP$1)") (class "Default")
      (node (ref "R8") (pin "P$1") (pinfunction "P$1_P$1") (pintype "bidirectional"))
      (node (ref "R9") (pin "P$2") (pinfunction "P$2_P$2") (pintype "bidirectional"))
      (node (ref "U3") (pin "11") (pinfunction "FB_11") (pintype "bidirectional"))
    )
    (net (code "45") (name "Net-(R10-PadP$1)") (class "Default")
      (node (ref "R10") (pin "P$1") (pinfunction "P$1_P$1") (pintype "bidirectional"))
      (node (ref "U3") (pin "18") (pinfunction "EN_18") (pintype "bidirectional"))
    )
    (net (code "46") (name "Net-(R12-PadP$2)") (class "Default")
      (node (ref "R12") (pin "P$2") (pinfunction "P$2_P$2") (pintype "bidirectional"))
      (node (ref "R13") (pin "P$1") (pinfunction "P$1_P$1") (pintype "bidirectional"))
      (node (ref "U3") (pin "16") (pinfunction "FB_16") (pintype "bidirectional"))
    )
    (net (code "47") (name "Net-(U1-DECOUPLE)") (class "Default")
      (node (ref "C23") (pin "P$1") (pinfunction "P$1_P$1") (pintype "bidirectional"))
      (node (ref "U1") (pin "40") (pinfunction "DECOUPLE_40") (pintype "bidirectional"))
    )
    (net (code "48") (name "Net-(U1-VREGO)") (class "Default")
      (node (ref "C17") (pin "P$1") (pinfunction "P$1_P$1") (pintype "bidirectional"))
      (node (ref "U1") (pin "46") (pinfunction "VREGO_46") (pintype "bidirectional"))
    )
    (net (code "49") (name "Net-(U2-VPP_2V5)") (class "Default")
      (node (ref "C7") (pin "P$1") (pinfunction "P$1_P$1") (pintype "bidirectional"))
      (node (ref "D2") (pin "C") (pinfunction "C_C") (pintype "passive"))
      (node (ref "U2") (pin "24") (pinfunction "VPP_2V5_24") (pintype "bidirectional"))
    )
    (net (code "50") (name "Net-(USB1-SB1)") (class "Default")
      (node (ref "R16") (pin "P$2") (pinfunction "P$2_P$2") (pintype "bidirectional"))
      (node (ref "USB1") (pin "A8") (pinfunction "SB1_A8") (pintype "bidirectional"))
    )
    (net (code "51") (name "Net-(USB1-SB2)") (class "Default")
      (node (ref "R15") (pin "P$2") (pinfunction "P$2_P$2") (pintype "bidirectional"))
      (node (ref "USB1") (pin "B8") (pinfunction "SB2_B8") (pintype "bidirectional"))
    )
    (net (code "52") (name "PD3") (class "Default")
      (node (ref "J3") (pin "2") (pinfunction "S_2") (pintype "passive"))
      (node (ref "U1") (pin "31") (pinfunction "PD3_31") (pintype "bidirectional"))
    )
    (net (code "53") (name "PD4") (class "Default")
      (node (ref "J3") (pin "3") (pinfunction "S_3") (pintype "passive"))
      (node (ref "U1") (pin "32") (pinfunction "PD4_32") (pintype "bidirectional"))
    )
    (net (code "54") (name "PD5") (class "Default")
      (node (ref "J3") (pin "4") (pinfunction "S_4") (pintype "passive"))
      (node (ref "U1") (pin "33") (pinfunction "PD5_33") (pintype "bidirectional"))
    )
    (net (code "55") (name "PD6") (class "Default")
      (node (ref "J3") (pin "5") (pinfunction "S_5") (pintype "passive"))
      (node (ref "U1") (pin "34") (pinfunction "PD6_34") (pintype "bidirectional"))
    )
    (net (code "56") (name "PE4") (class "Default")
      (node (ref "J3") (pin "6") (pinfunction "S_6") (pintype "passive"))
      (node (ref "U1") (pin "41") (pinfunction "PE4_41") (pintype "bidirectional"))
    )
    (net (code "57") (name "PE5") (class "Default")
      (node (ref "J3") (pin "7") (pinfunction "S_7") (pintype "passive"))
      (node (ref "U1") (pin "42") (pinfunction "PE5_42") (pintype "bidirectional"))
    )
    (net (code "58") (name "PE6") (class "Default")
      (node (ref "J5") (pin "8") (pinfunction "S_8") (pintype "passive"))
      (node (ref "U1") (pin "43") (pinfunction "PE6_43") (pintype "bidirectional"))
    )
    (net (code "59") (name "PE7") (class "Default")
      (node (ref "J5") (pin "7") (pinfunction "S_7") (pintype "passive"))
      (node (ref "U1") (pin "44") (pinfunction "PE7_44") (pintype "bidirectional"))
    )
    (net (code "60") (name "PE8") (class "Default")
      (node (ref "J5") (pin "6") (pinfunction "S_6") (pintype "passive"))
      (node (ref "U1") (pin "56") (pinfunction "PE8_56") (pintype "bidirectional"))
    )
    (net (code "61") (name "PE9") (class "Default")
      (node (ref "J5") (pin "5") (pinfunction "S_5") (pintype "passive"))
      (node (ref "U1") (pin "57") (pinfunction "PE9_57") (pintype "bidirectional"))
    )
    (net (code "62") (name "PE10") (class "Default")
      (node (ref "J5") (pin "4") (pinfunction "S_4") (pintype "passive"))
      (node (ref "U1") (pin "58") (pinfunction "PE10_58") (pintype "bidirectional"))
    )
    (net (code "63") (name "PE11") (class "Default")
      (node (ref "J5") (pin "3") (pinfunction "S_3") (pintype "passive"))
      (node (ref "U1") (pin "59") (pinfunction "PE11_59") (pintype "bidirectional"))
    )
    (net (code "64") (name "PE12") (class "Default")
      (node (ref "J5") (pin "2") (pinfunction "S_2") (pintype "passive"))
      (node (ref "U1") (pin "60") (pinfunction "PE12_60") (pintype "bidirectional"))
    )
    (net (code "65") (name "PE13") (class "Default")
      (node (ref "J5") (pin "1") (pinfunction "S_1") (pintype "passive"))
      (node (ref "U1") (pin "61") (pinfunction "PE13_61") (pintype "bidirectional"))
    )
    (net (code "66") (name "PF12") (class "Default")
      (node (ref "J3") (pin "8") (pinfunction "S_8") (pintype "passive"))
      (node (ref "U1") (pin "53") (pinfunction "PF12_53") (pintype "bidirectional"))
    )
    (net (code "67") (name "QSPI_CLK") (class "Default")
      (node (ref "U1") (pin "62") (pinfunction "PE14_62") (pintype "bidirectional"))
      (node (ref "U6") (pin "6") (pinfunction "SCK_6") (pintype "input"))
    )
    (net (code "68") (name "QSPI_CS0") (class "Default")
      (node (ref "R17") (pin "P$1") (pinfunction "P$1_P$1") (pintype "bidirectional"))
      (node (ref "U1") (pin "1") (pinfunction "PA0_1") (pintype "bidirectional"))
      (node (ref "U6") (pin "1") (pinfunction "~{CS}_1") (pintype "input"))
    )
    (net (code "69") (name "QSPI_D0") (class "Default")
      (node (ref "U1") (pin "3") (pinfunction "PA2_3") (pintype "bidirectional"))
      (node (ref "U6") (pin "5") (pinfunction "MOSI/IO0_5") (pintype "input"))
    )
    (net (code "70") (name "QSPI_D1") (class "Default")
      (node (ref "U1") (pin "4") (pinfunction "PA3_4") (pintype "bidirectional"))
      (node (ref "U6") (pin "2") (pinfunction "MISO/IO1_2") (pintype "output"))
    )
    (net (code "71") (name "QSPI_D2") (class "Default")
      (node (ref "U1") (pin "5") (pinfunction "PA4_5") (pintype "bidirectional"))
      (node (ref "U6") (pin "3") (pinfunction "~{WP}/IO2_3") (pintype "input"))
    )
    (net (code "72") (name "QSPI_D3") (class "Default")
      (node (ref "U1") (pin "6") (pinfunction "PA5_6") (pintype "bidirectional"))
      (node (ref "U6") (pin "7") (pinfunction "~{HOLD}/IO3_7") (pintype "input"))
    )
    (net (code "73") (name "SCK") (class "Default")
      (node (ref "U1") (pin "11") (pinfunction "PB5_11") (pintype "bidirectional"))
      (node (ref "U2") (pin "15") (pinfunction "IOB_26_SCK_15") (pintype "bidirectional"))
    )
    (net (code "74") (name "SS") (class "Default")
      (node (ref "U1") (pin "12") (pinfunction "PB6_12") (pintype "bidirectional"))
      (node (ref "U2") (pin "14") (pinfunction "IOB_27_SS_14") (pintype "bidirectional"))
    )
    (net (code "75") (name "SWCLK") (class "Default")
      (node (ref "TC1") (pin "4") (pinfunction "S_4") (pintype "passive"))
      (node (ref "U1") (pin "49") (pinfunction "PF0_49") (pintype "bidirectional"))
    )
    (net (code "76") (name "SWDIO") (class "Default")
      (node (ref "TC1") (pin "2") (pinfunction "S_2") (pintype "passive"))
      (node (ref "U1") (pin "50") (pinfunction "PF1_50") (pintype "bidirectional"))
    )
    (net (code "77") (name "SWO") (class "Default")
      (node (ref "TC1") (pin "6") (pinfunction "S_6") (pintype "passive"))
      (node (ref "U1") (pin "51") (pinfunction "PF2_51") (pintype "bidirectional"))
    )
    (net (code "78") (name "VUSB") (class "Default")
      (node (ref "C12") (pin "P$1") (pinfunction "P$1_P$1") (pintype "bidirectional"))
      (node (ref "C15") (pin "P$1") (pinfunction "P$1_P$1") (pintype "bidirectional"))
      (node (ref "C16") (pin "P$1") (pinfunction "P$1_P$1") (pintype "bidirectional"))
      (node (ref "C25") (pin "P$1") (pinfunction "P$1_P$1") (pintype "bidirectional"))
      (node (ref "C8") (pin "P$1") (pinfunction "P$1_P$1") (pintype "bidirectional"))
      (node (ref "C9") (pin "P$1") (pinfunction "P$1_P$1") (pintype "bidirectional"))
      (node (ref "D1") (pin "5") (pinfunction "VDD_5") (pintype "bidirectional"))
      (node (ref "D3") (pin "3") (pinfunction "3_3") (pintype "bidirectional"))
      (node (ref "F1") (pin "1") (pinfunction "1_1") (pintype "passive"))
      (node (ref "J6") (pin "3") (pinfunction "S_3") (pintype "passive"))
      (node (ref "J7") (pin "3") (pinfunction "S_3") (pintype "passive"))
      (node (ref "R10") (pin "P$2") (pinfunction "P$2_P$2") (pintype "bidirectional"))
      (node (ref "R7") (pin "P$2") (pinfunction "P$2_P$2") (pintype "bidirectional"))
      (node (ref "U1") (pin "52") (pinfunction "VBUS_52") (pintype "bidirectional"))
      (node (ref "U3") (pin "1") (pinfunction "VIN_1") (pintype "bidirectional"))
      (node (ref "U3") (pin "20") (pinfunction "AVIN_20") (pintype "bidirectional"))
      (node (ref "U3") (pin "6") (pinfunction "VIN_6") (pintype "bidirectional"))
      (node (ref "U3") (pin "7") (pinfunction "AVIN_7") (pintype "bidirectional"))
    )
    (net (code "79") (name "unconnected-(D1-CLKO-Pad6)") (class "Default")
      (node (ref "D1") (pin "6") (pinfunction "CLKO_6") (pintype "bidirectional"))
    )
    (net (code "80") (name "unconnected-(D1-SDO-Pad1)") (class "Default")
      (node (ref "D1") (pin "1") (pinfunction "SDO_1") (pintype "bidirectional"))
    )
    (net (code "81") (name "unconnected-(SW1-Pad2)") (class "Default")
      (node (ref "SW1") (pin "2") (pinfunction "2_2") (pintype "passive"))
    )
    (net (code "82") (name "unconnected-(TC1F-S-Pad5)") (class "Default")
      (node (ref "TC1") (pin "5") (pinfunction "S_5") (pintype "passive"))
    )
    (net (code "83") (name "unconnected-(TC1H-S-Pad7)") (class "Default")
      (node (ref "TC1") (pin "7") (pinfunction "S_7") (pintype "passive"))
    )
    (net (code "84") (name "unconnected-(TC1I-S-Pad8)") (class "Default")
      (node (ref "TC1") (pin "8") (pinfunction "S_8") (pintype "passive"))
    )
    (net (code "85") (name "unconnected-(U1-PA1-Pad2)") (class "Default")
      (node (ref "U1") (pin "2") (pinfunction "PA1_2") (pintype "bidirectional"))
    )
    (net (code "86") (name "unconnected-(U1-PA14-Pad20)") (class "Default")
      (node (ref "U1") (pin "20") (pinfunction "PA14_20") (pintype "bidirectional"))
    )
    (net (code "87") (name "unconnected-(U1-PA15-Pad64)") (class "Default")
      (node (ref "U1") (pin "64") (pinfunction "PA15_64") (pintype "bidirectional"))
    )
    (net (code "88") (name "unconnected-(U1-PB11-Pad22)") (class "Default")
      (node (ref "U1") (pin "22") (pinfunction "PB11_22") (pintype "bidirectional"))
    )
    (net (code "89") (name "unconnected-(U1-PB12-Pad23)") (class "Default")
      (node (ref "U1") (pin "23") (pinfunction "PB12_23") (pintype "bidirectional"))
    )
    (net (code "90") (name "unconnected-(U1-PC4-Pad13)") (class "Default")
      (node (ref "U1") (pin "13") (pinfunction "PC4_13") (pintype "bidirectional"))
    )
    (net (code "91") (name "unconnected-(U1-PC5-Pad14)") (class "Default")
      (node (ref "U1") (pin "14") (pinfunction "PC5_14") (pintype "bidirectional"))
    )
    (net (code "92") (name "unconnected-(U1-PE15-Pad63)") (class "Default")
      (node (ref "U1") (pin "63") (pinfunction "PE15_63") (pintype "bidirectional"))
    )
    (net (code "93") (name "unconnected-(U1-PF5-Pad54)") (class "Default")
      (node (ref "U1") (pin "54") (pinfunction "PF5_54") (pintype "bidirectional"))
    )
    (net (code "94") (name "unconnected-(U1-VREGI-Pad45)") (class "Default")
      (node (ref "U1") (pin "45") (pinfunction "VREGI_45") (pintype "bidirectional"))
    )
    (net (code "95") (name "unconnected-(USB1-CC1-PadA5)") (class "Default")
      (node (ref "USB1") (pin "A5") (pinfunction "CC1_A5") (pintype "bidirectional"))
    )
    (net (code "96") (name "unconnected-(USB1-CC2-PadB5)") (class "Default")
      (node (ref "USB1") (pin "B5") (pinfunction "CC2_B5") (pintype "bidirectional"))
    )
    (net (code "97") (name "~{CRESET}") (class "Default")
      (node (ref "R6") (pin "P$2") (pinfunction "P$2_P$2") (pintype "bidirectional"))
      (node (ref "U1") (pin "7") (pinfunction "PA6_7") (pintype "bidirectional"))
      (node (ref "U2") (pin "10") (pinfunction "~{CRESET_B}_10") (pintype "bidirectional"))
    )
    (net (code "98") (name "~{MCU_RESET}") (class "Default")
      (node (ref "R1") (pin "P$1") (pinfunction "P$1_P$1") (pintype "bidirectional"))
      (node (ref "SW1") (pin "1") (pinfunction "1_1") (pintype "passive"))
      (node (ref "TC1") (pin "10") (pinfunction "S_10") (pintype "passive"))
      (node (ref "U1") (pin "21") (pinfunction "~{RESET}_21") (pintype "bidirectional"))
    )
  )
)
